# TM4C.net
KiCad netlist of a schematic drawn in Altium Designer
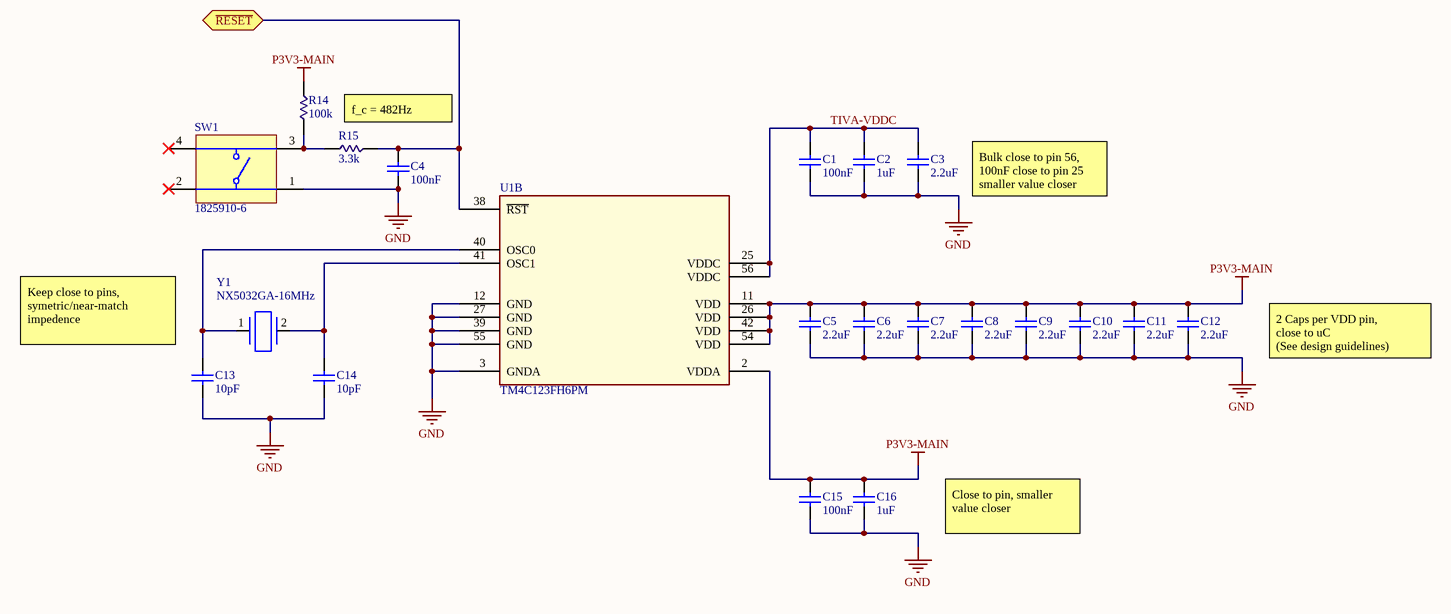
[diagram p0: TM4C.SchDoc]

(export (version "E")
  (design (tool "Eeschema 10.0.6"))
  (components
    (comp (ref "C1")
      (value "100nF")
      (footprint "FOOTPRINT-0805-GEN")
      (description "Capacitor")
      (fields (field (name "Comment") "C0805C104K8RACTU") (field (name "PUBLISHER") "Altium Limited"))
      (libsource (lib "HR-Master-Integrated") (part "Capacitor-Generic-0805"))
    )
    (comp (ref "C2")
      (value "1uF")
      (footprint "FOOTPRINT-0805-GEN")
      (description "Capacitor")
      (fields (field (name "Comment") "C0805C105K8RACTU") (field (name "PUBLISHER") "Altium Limited"))
      (libsource (lib "HR-Master-Integrated") (part "Capacitor-Generic-0805"))
    )
    (comp (ref "C3")
      (value "2.2uF")
      (footprint "FOOTPRINT-0805-GEN")
      (description "Capacitor")
      (fields (field (name "Comment") "C0805C225K8RACTU") (field (name "PUBLISHER") "Altium Limited"))
      (libsource (lib "HR-Master-Integrated") (part "Capacitor-Generic-0805"))
    )
    (comp (ref "C4")
      (value "100nF")
      (footprint "FOOTPRINT-0805-GEN")
      (description "Capacitor")
      (fields (field (name "Comment") "C0805C104K8RACTU") (field (name "PUBLISHER") "Altium Limited"))
      (libsource (lib "HR-Master-Integrated") (part "Capacitor-Generic-0805"))
    )
    (comp (ref "C5")
      (value "2.2uF")
      (footprint "FOOTPRINT-0805-GEN")
      (description "Capacitor")
      (fields (field (name "Comment") "C0805C225K8RACTU") (field (name "PUBLISHER") "Altium Limited"))
      (libsource (lib "HR-Master-Integrated") (part "Capacitor-Generic-0805"))
    )
    (comp (ref "C6")
      (value "2.2uF")
      (footprint "FOOTPRINT-0805-GEN")
      (description "Capacitor")
      (fields (field (name "Comment") "C0805C225K8RACTU") (field (name "PUBLISHER") "Altium Limited"))
      (libsource (lib "HR-Master-Integrated") (part "Capacitor-Generic-0805"))
    )
    (comp (ref "C7")
      (value "2.2uF")
      (footprint "FOOTPRINT-0805-GEN")
      (description "Capacitor")
      (fields (field (name "Comment") "C0805C225K8RACTU") (field (name "PUBLISHER") "Altium Limited"))
      (libsource (lib "HR-Master-Integrated") (part "Capacitor-Generic-0805"))
    )
    (comp (ref "C8")
      (value "2.2uF")
      (footprint "FOOTPRINT-0805-GEN")
      (description "Capacitor")
      (fields (field (name "Comment") "C0805C225K8RACTU") (field (name "PUBLISHER") "Altium Limited"))
      (libsource (lib "HR-Master-Integrated") (part "Capacitor-Generic-0805"))
    )
    (comp (ref "C9")
      (value "2.2uF")
      (footprint "FOOTPRINT-0805-GEN")
      (description "Capacitor")
      (fields (field (name "Comment") "C0805C225K8RACTU") (field (name "PUBLISHER") "Altium Limited"))
      (libsource (lib "HR-Master-Integrated") (part "Capacitor-Generic-0805"))
    )
    (comp (ref "C10")
      (value "2.2uF")
      (footprint "FOOTPRINT-0805-GEN")
      (description "Capacitor")
      (fields (field (name "Comment") "C0805C225K8RACTU") (field (name "PUBLISHER") "Altium Limited"))
      (libsource (lib "HR-Master-Integrated") (part "Capacitor-Generic-0805"))
    )
    (comp (ref "C11")
      (value "2.2uF")
      (footprint "FOOTPRINT-0805-GEN")
      (description "Capacitor")
      (fields (field (name "Comment") "C0805C225K8RACTU") (field (name "PUBLISHER") "Altium Limited"))
      (libsource (lib "HR-Master-Integrated") (part "Capacitor-Generic-0805"))
    )
    (comp (ref "C12")
      (value "2.2uF")
      (footprint "FOOTPRINT-0805-GEN")
      (description "Capacitor")
      (fields (field (name "Comment") "C0805C225K8RACTU") (field (name "PUBLISHER") "Altium Limited"))
      (libsource (lib "HR-Master-Integrated") (part "Capacitor-Generic-0805"))
    )
    (comp (ref "C13")
      (value "10pF")
      (footprint "FOOTPRINT-0805-GEN")
      (description "Capacitor")
      (fields (field (name "Comment") "C0805C100K5RAC7800") (field (name "PUBLISHER") "Altium Limited"))
      (libsource (lib "HR-Master-Integrated") (part "Capacitor-Generic-0805"))
    )
    (comp (ref "C14")
      (value "10pF")
      (footprint "FOOTPRINT-0805-GEN")
      (description "Capacitor")
      (fields (field (name "Comment") "C0805C100K5RAC7800") (field (name "PUBLISHER") "Altium Limited"))
      (libsource (lib "HR-Master-Integrated") (part "Capacitor-Generic-0805"))
    )
    (comp (ref "C15")
      (value "100nF")
      (footprint "FOOTPRINT-0805-GEN")
      (description "Capacitor")
      (fields (field (name "Comment") "C0805C104K8RACTU") (field (name "PUBLISHER") "Altium Limited"))
      (libsource (lib "HR-Master-Integrated") (part "Capacitor-Generic-0805"))
    )
    (comp (ref "C16")
      (value "1uF")
      (footprint "FOOTPRINT-0805-GEN")
      (description "Capacitor")
      (fields (field (name "Comment") "C0805C105K8RACTU") (field (name "PUBLISHER") "Altium Limited"))
      (libsource (lib "HR-Master-Integrated") (part "Capacitor-Generic-0805"))
    )
    (comp (ref "R14")
      (value "100k")
      (footprint "FOOTPRINT-0805-GEN")
      (description "1/8 Watt Surface Mount Resistor")
      (fields (field (name "Comment") "SMC"))
      (libsource (lib "HR-Master-Integrated") (part "Resistor-Generic-0805-2012"))
    )
    (comp (ref "R15")
      (value "3.3k")
      (footprint "FOOTPRINT-0805-GEN")
      (description "1/8 Watt Surface Mount Resistor")
      (fields (field (name "Comment") "SMC"))
      (libsource (lib "HR-Master-Integrated") (part "Resistor-Generic-0805-2012"))
    )
    (comp (ref "SW1")
      (value "1825910-6")
      (footprint "TECO-1825910-6_V")
      (description "Tact Switch, SPST-NO, 0.05 A, -35 to 85 degC, 4-Pin THD, RoHS, Bulk")
      (fields (field (name "MANUFACTURER") "TE Connectivity"))
      (libsource (lib "Altium Content Vault") (part "SW-SPST-4_A"))
    )
    (comp (ref "U1")
      (value "TM4C123FH6PM")
      (footprint "FOOTPRINT-TI-TM4C123-64-LQFP")
      (libsource (lib "HR-Master-Integrated") (part "IC-TI-TM4C123FH6PM"))
    )
    (comp (ref "Y1")
      (value "NX5032GA-16.000000MHZ-LN-CD-1")
      (footprint "FOOTPRINT-NDK-NX5032GA")
      (fields (field (name "NAMESHORT") "NX5032GA-16MHz"))
      (libsource (lib "HR-Master-Integrated") (part "Crystal-NDK-NX5032GA-16MHz"))
    )
  )
  (nets
    (net (code "1") (name "/RESET") (class "Default")
      (node (ref "C4") (pin "2") (pinfunction "2_2") (pintype "passive"))
      (node (ref "R15") (pin "2") (pinfunction "2_2") (pintype "passive"))
      (node (ref "U1") (pin "38") (pinfunction "~{RST}_38") (pintype "passive"))
    )
    (net (code "2") (name "/TIVA-VDDC") (class "Default")
      (node (ref "C1") (pin "2") (pinfunction "2_2") (pintype "passive"))
      (node (ref "C2") (pin "2") (pinfunction "2_2") (pintype "passive"))
      (node (ref "C3") (pin "1") (pinfunction "1_1") (pintype "passive"))
      (node (ref "U1") (pin "25") (pinfunction "VDDC_25") (pintype "passive"))
      (node (ref "U1") (pin "56") (pinfunction "VDDC_56") (pintype "passive"))
    )
    (net (code "3") (name "GND") (class "Default")
      (node (ref "C1") (pin "1") (pinfunction "1_1") (pintype "passive"))
      (node (ref "C10") (pin "2") (pinfunction "2_2") (pintype "passive"))
      (node (ref "C11") (pin "2") (pinfunction "2_2") (pintype "passive"))
      (node (ref "C12") (pin "2") (pinfunction "2_2") (pintype "passive"))
      (node (ref "C13") (pin "2") (pinfunction "2_2") (pintype "passive"))
      (node (ref "C14") (pin "2") (pinfunction "2_2") (pintype "passive"))
      (node (ref "C15") (pin "1") (pinfunction "1_1") (pintype "passive"))
      (node (ref "C16") (pin "1") (pinfunction "1_1") (pintype "passive"))
      (node (ref "C2") (pin "1") (pinfunction "1_1") (pintype "passive"))
      (node (ref "C3") (pin "2") (pinfunction "2_2") (pintype "passive"))
      (node (ref "C4") (pin "1") (pinfunction "1_1") (pintype "passive"))
      (node (ref "C5") (pin "2") (pinfunction "2_2") (pintype "passive"))
      (node (ref "C6") (pin "2") (pinfunction "2_2") (pintype "passive"))
      (node (ref "C7") (pin "2") (pinfunction "2_2") (pintype "passive"))
      (node (ref "C8") (pin "2") (pinfunction "2_2") (pintype "passive"))
      (node (ref "C9") (pin "2") (pinfunction "2_2") (pintype "passive"))
      (node (ref "SW1") (pin "1") (pinfunction "1_1") (pintype "passive"))
      (node (ref "U1") (pin "12") (pinfunction "GND_12") (pintype "passive"))
      (node (ref "U1") (pin "27") (pinfunction "GND_27") (pintype "passive"))
      (node (ref "U1") (pin "3") (pinfunction "GNDA_3") (pintype "passive"))
      (node (ref "U1") (pin "39") (pinfunction "GND_39") (pintype "passive"))
      (node (ref "U1") (pin "55") (pinfunction "GND_55") (pintype "passive"))
    )
    (net (code "4") (name "Net-(R14-Pad1)") (class "Default")
      (node (ref "R14") (pin "1") (pinfunction "1_1") (pintype "passive"))
      (node (ref "R15") (pin "1") (pinfunction "1_1") (pintype "passive"))
      (node (ref "SW1") (pin "3") (pinfunction "3_3") (pintype "passive"))
    )
    (net (code "5") (name "Net-(U1B-OSC0)") (class "Default")
      (node (ref "C13") (pin "1") (pinfunction "1_1") (pintype "passive"))
      (node (ref "U1") (pin "40") (pinfunction "OSC0_40") (pintype "passive"))
      (node (ref "Y1") (pin "1") (pinfunction "X1_1") (pintype "passive"))
    )
    (net (code "6") (name "Net-(U1B-OSC1)") (class "Default")
      (node (ref "C14") (pin "1") (pinfunction "1_1") (pintype "passive"))
      (node (ref "U1") (pin "41") (pinfunction "OSC1_41") (pintype "passive"))
      (node (ref "Y1") (pin "2") (pinfunction "X2_2") (pintype "passive"))
    )
    (net (code "7") (name "P3V3-MAIN") (class "Default")
      (node (ref "C10") (pin "1") (pinfunction "1_1") (pintype "passive"))
      (node (ref "C11") (pin "1") (pinfunction "1_1") (pintype "passive"))
      (node (ref "C12") (pin "1") (pinfunction "1_1") (pintype "passive"))
      (node (ref "C15") (pin "2") (pinfunction "2_2") (pintype "passive"))
      (node (ref "C16") (pin "2") (pinfunction "2_2") (pintype "passive"))
      (node (ref "C5") (pin "1") (pinfunction "1_1") (pintype "passive"))
      (node (ref "C6") (pin "1") (pinfunction "1_1") (pintype "passive"))
      (node (ref "C7") (pin "1") (pinfunction "1_1") (pintype "passive"))
      (node (ref "C8") (pin "1") (pinfunction "1_1") (pintype "passive"))
      (node (ref "C9") (pin "1") (pinfunction "1_1") (pintype "passive"))
      (node (ref "R14") (pin "2") (pinfunction "2_2") (pintype "passive"))
      (node (ref "U1") (pin "11") (pinfunction "VDD_11") (pintype "passive"))
      (node (ref "U1") (pin "2") (pinfunction "VDDA_2") (pintype "passive"))
      (node (ref "U1") (pin "26") (pinfunction "VDD_26") (pintype "passive"))
      (node (ref "U1") (pin "42") (pinfunction "VDD_42") (pintype "passive"))
      (node (ref "U1") (pin "54") (pinfunction "VDD_54") (pintype "passive"))
    )
    (net (code "8") (name "unconnected-(SW1-Pad2)") (class "Default")
      (node (ref "SW1") (pin "2") (pinfunction "2_2") (pintype "passive+no_connect"))
    )
    (net (code "9") (name "unconnected-(SW1-Pad4)") (class "Default")
      (node (ref "SW1") (pin "4") (pinfunction "4_4") (pintype "passive+no_connect"))
    )
  )
)
